# Sheet3.net
KiCad netlist of a schematic drawn in Altium Designer
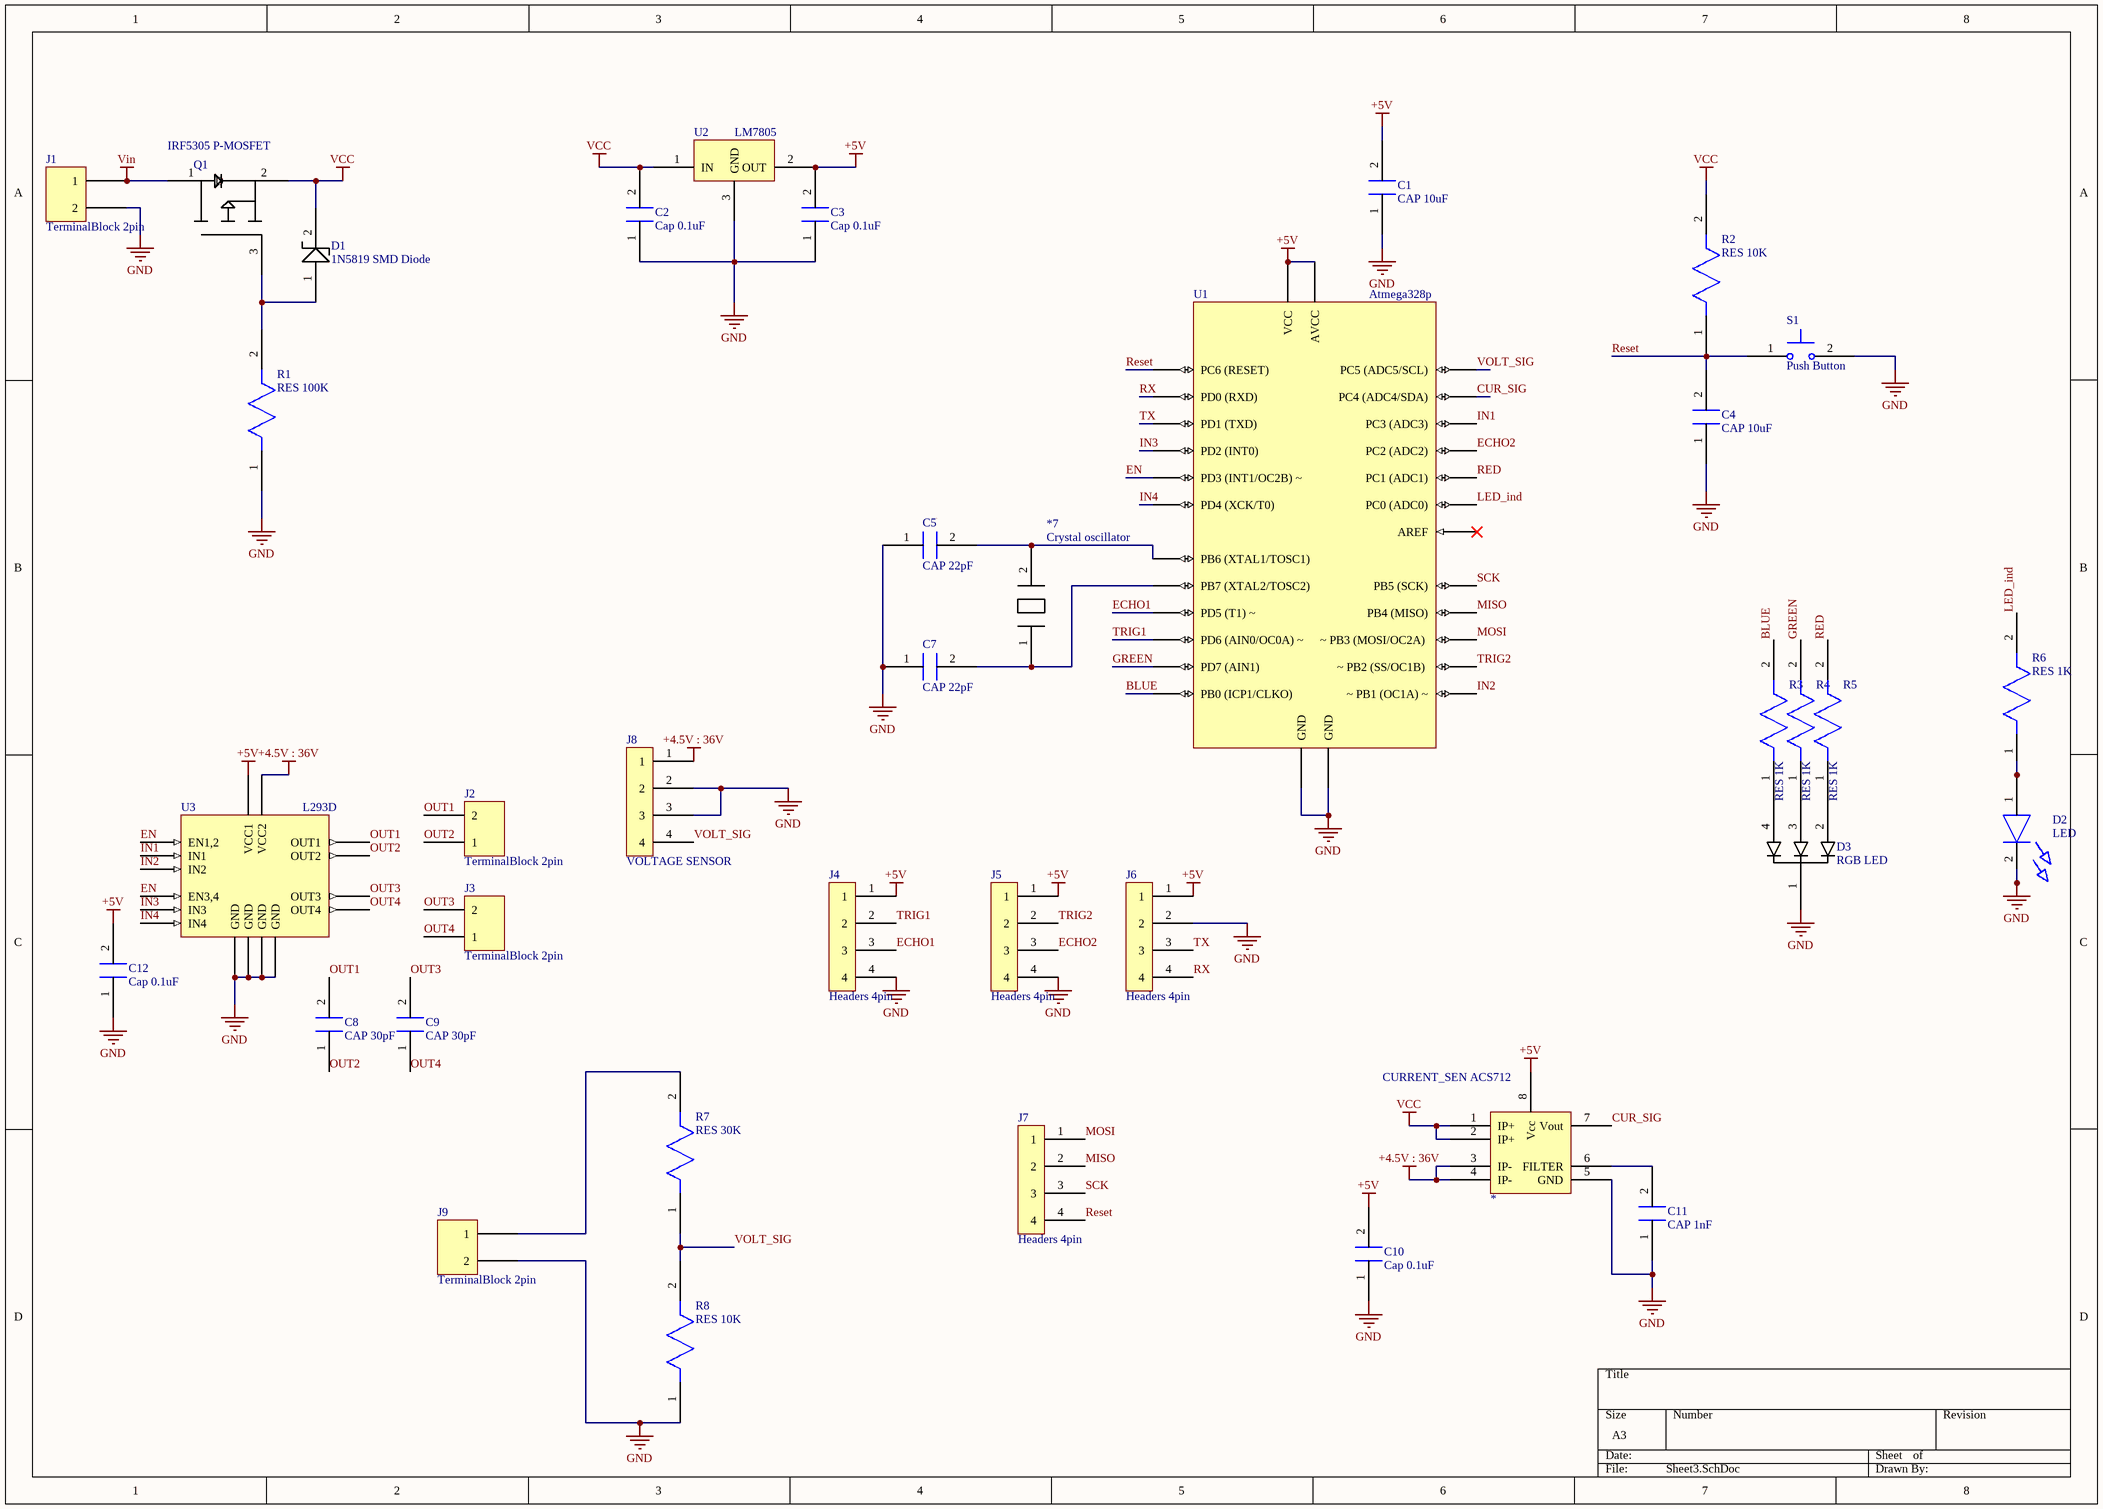
[diagram p0: Sheet3.SchDoc]

(export (version "E")
  (design (tool "Eeschema 10.0.6"))
  (components
    (comp (ref "*")
      (value "CURRENT_SEN ACS712")
      (footprint "Cuurent_sens")
      (libsource (lib "Schlib1") (part "CURRENT_MOD ACS712"))
    )
    (comp (ref "*7")
      (value "Crystal oscillator")
      (footprint "Crrystal 16MHZ")
      (libsource (lib "Schlib1") (part "Crystal oscillator"))
    )
    (comp (ref "C1") (value "CAP 10uF") (footprint "Cap 10uF") (libsource (lib "Schlib1") (part "CAP 10uF")))
    (comp (ref "C2")
      (value "Cap 0.1uF")
      (footprint "CAP 0.1uF")
      (libsource (lib "Schlib1") (part "Cap 0.1uF"))
    )
    (comp (ref "C3")
      (value "Cap 0.1uF")
      (footprint "CAP 0.1uF")
      (libsource (lib "Schlib1") (part "Cap 0.1uF"))
    )
    (comp (ref "C4") (value "CAP 10uF") (footprint "Cap 10uF") (libsource (lib "Schlib1") (part "CAP 10uF")))
    (comp (ref "C5") (value "CAP 22pF") (footprint "Cap 22pF") (libsource (lib "Schlib1") (part "CAP 22pF")))
    (comp (ref "C7") (value "CAP 22pF") (footprint "Cap 22pF") (libsource (lib "Schlib1") (part "CAP 22pF")))
    (comp (ref "C8") (value "CAP 30pF") (footprint "CAP 30pF") (libsource (lib "Schlib1") (part "CAP 30pF")))
    (comp (ref "C9") (value "CAP 30pF") (footprint "CAP 30pF") (libsource (lib "Schlib1") (part "CAP 30pF")))
    (comp (ref "C10")
      (value "Cap 0.1uF")
      (footprint "CAP 0.1uF")
      (libsource (lib "Schlib1") (part "Cap 0.1uF"))
    )
    (comp (ref "C11") (value "CAP 1nF") (footprint "CAP 1nF") (libsource (lib "Schlib1") (part "CAP 1nF")))
    (comp (ref "C12")
      (value "Cap 0.1uF")
      (footprint "CAP 0.1uF")
      (libsource (lib "Schlib1") (part "Cap 0.1uF"))
    )
    (comp (ref "D1")
      (value "1N5819 SMD Diode")
      (footprint "1N5819 SMD Diode")
      (libsource (lib "Schlib1") (part "1N5819 SMD Diode"))
    )
    (comp (ref "D2") (value "LED") (footprint "LED") (libsource (lib "Schlib1") (part "LED")))
    (comp (ref "D3") (value "RGB LED") (footprint "RGB LED") (libsource (lib "Schlib1") (part "RGB LED")))
    (comp (ref "J1")
      (value "TerminalBlock 2pin")
      (footprint "Terminal Block 2pin")
      (libsource (lib "Schlib1") (part "TerminalBlock 2pin"))
    )
    (comp (ref "J2")
      (value "TerminalBlock 2pin")
      (footprint "Terminal Block 2pin")
      (libsource (lib "") (part "TerminalBlock 2pin_1"))
    )
    (comp (ref "J3")
      (value "TerminalBlock 2pin")
      (footprint "Terminal Block 2pin")
      (libsource (lib "") (part "TerminalBlock 2pin_1"))
    )
    (comp (ref "J4")
      (value "Headers 4pin")
      (footprint "Header 4pin")
      (libsource (lib "Schlib1") (part "Headers 4pin"))
    )
    (comp (ref "J5")
      (value "Headers 4pin")
      (footprint "Header 4pin")
      (libsource (lib "Schlib1") (part "Headers 4pin"))
    )
    (comp (ref "J6")
      (value "Headers 4pin")
      (footprint "Header 4pin")
      (libsource (lib "Schlib1") (part "Headers 4pin"))
    )
    (comp (ref "J7")
      (value "Headers 4pin")
      (footprint "Header 4pin")
      (libsource (lib "Schlib1") (part "Headers 4pin"))
    )
    (comp (ref "J8")
      (value "VOLTAGE SENSOR")
      (footprint "Header 4pin")
      (libsource (lib "Schlib1") (part "Headers 4pin"))
    )
    (comp (ref "J9")
      (value "TerminalBlock 2pin")
      (footprint "Terminal Block 2pin")
      (libsource (lib "Schlib1") (part "TerminalBlock 2pin"))
    )
    (comp (ref "Q1")
      (value "IRF5305 P-MOSFET")
      (footprint "IRF5305")
      (libsource (lib "Schlib1") (part "IRF5305 P-MOSFET"))
    )
    (comp (ref "R1") (value "RES 100K") (footprint "Res100K") (libsource (lib "Schlib1") (part "RES 100K")))
    (comp (ref "R2") (value "RES 10K") (footprint "Res10K") (libsource (lib "Schlib1") (part "RES 10K")))
    (comp (ref "R3") (value "RES 1K") (footprint "Res 1K") (libsource (lib "Schlib1") (part "RES 1K")))
    (comp (ref "R4") (value "RES 1K") (footprint "Res 1K") (libsource (lib "Schlib1") (part "RES 1K")))
    (comp (ref "R5") (value "RES 1K") (footprint "Res 1K") (libsource (lib "Schlib1") (part "RES 1K")))
    (comp (ref "R6") (value "RES 1K") (footprint "Res 1K") (libsource (lib "Schlib1") (part "RES 1K")))
    (comp (ref "R7") (value "RES 30K") (footprint "Res100K") (libsource (lib "Schlib1") (part "RES 100K")))
    (comp (ref "R8") (value "RES 10K") (footprint "Res10K") (libsource (lib "Schlib1") (part "RES 10K")))
    (comp (ref "S1")
      (value "Push Button")
      (footprint "Push Button")
      (libsource (lib "Schlib1") (part "Push Button"))
    )
    (comp (ref "U1")
      (value "Atmega328p")
      (footprint "ATMega 328 P-PU - duplicate")
      (libsource (lib "Schlib1") (part "Atmega328p"))
    )
    (comp (ref "U2") (value "LM7805") (footprint "LM7805") (libsource (lib "Schlib1") (part "LM7805")))
    (comp (ref "U3") (value "L293D") (footprint "L293D") (libsource (lib "Schlib1") (part "L293D")))
  )
  (nets
    (net (code "1") (name "+4.5V : 36V") (class "Default")
      (node (ref "*") (pin "3") (pinfunction "IP-_3") (pintype "passive"))
      (node (ref "*") (pin "4") (pinfunction "IP-_4") (pintype "passive"))
      (node (ref "J8") (pin "1") (pinfunction "1_1") (pintype "passive"))
      (node (ref "U3") (pin "8") (pinfunction "VCC2_8") (pintype "power_in"))
    )
    (net (code "2") (name "+5V") (class "Default")
      (node (ref "*") (pin "8") (pinfunction "Vcc_8") (pintype "passive"))
      (node (ref "C1") (pin "2") (pinfunction "2_2") (pintype "passive"))
      (node (ref "C10") (pin "2") (pinfunction "2_2") (pintype "passive"))
      (node (ref "C12") (pin "2") (pinfunction "2_2") (pintype "passive"))
      (node (ref "C3") (pin "2") (pinfunction "2_2") (pintype "passive"))
      (node (ref "J4") (pin "1") (pinfunction "1_1") (pintype "passive"))
      (node (ref "J5") (pin "1") (pinfunction "1_1") (pintype "passive"))
      (node (ref "J6") (pin "1") (pinfunction "1_1") (pintype "passive"))
      (node (ref "U1") (pin "20") (pinfunction "AVCC_20") (pintype "passive"))
      (node (ref "U1") (pin "7") (pinfunction "VCC_7") (pintype "passive"))
      (node (ref "U2") (pin "2") (pinfunction "OUT_2") (pintype "passive"))
      (node (ref "U3") (pin "16") (pinfunction "VCC1_16") (pintype "power_in"))
    )
    (net (code "4") (name "/BLUE") (class "Default")
      (node (ref "R3") (pin "2") (pinfunction "4_2") (pintype "passive"))
      (node (ref "U1") (pin "14") (pinfunction "PB0_(ICP1/CLKO)_14") (pintype "bidirectional"))
    )
    (net (code "5") (name "/CUR_SIG") (class "Default")
      (node (ref "*") (pin "7") (pinfunction "Vout_7") (pintype "passive"))
      (node (ref "U1") (pin "27") (pinfunction "PC4_(ADC4/SDA)_27") (pintype "bidirectional"))
    )
    (net (code "6") (name "/ECHO1") (class "Default")
      (node (ref "J4") (pin "3") (pinfunction "3_3") (pintype "passive"))
      (node (ref "U1") (pin "11") (pinfunction "PD5_(T1)_~_11") (pintype "bidirectional"))
    )
    (net (code "7") (name "/ECHO2") (class "Default")
      (node (ref "J5") (pin "3") (pinfunction "3_3") (pintype "passive"))
      (node (ref "U1") (pin "25") (pinfunction "PC2_(ADC2)_25") (pintype "bidirectional"))
    )
    (net (code "8") (name "/EN") (class "Default")
      (node (ref "U1") (pin "5") (pinfunction "PD3_(INT1/OC2B)_~_5") (pintype "bidirectional"))
      (node (ref "U3") (pin "1") (pinfunction "EN1,2_1") (pintype "input"))
      (node (ref "U3") (pin "9") (pinfunction "EN3,4_9") (pintype "input"))
    )
    (net (code "9") (name "/GREEN") (class "Default")
      (node (ref "R4") (pin "2") (pinfunction "4_2") (pintype "passive"))
      (node (ref "U1") (pin "13") (pinfunction "PD7_(AIN1)_13") (pintype "bidirectional"))
    )
    (net (code "10") (name "/IN1") (class "Default")
      (node (ref "U1") (pin "26") (pinfunction "PC3_(ADC3)_26") (pintype "bidirectional"))
      (node (ref "U3") (pin "2") (pinfunction "IN1_2") (pintype "input"))
    )
    (net (code "11") (name "/IN2") (class "Default")
      (node (ref "U1") (pin "15") (pinfunction "~_PB1_(OC1A)_~_15") (pintype "bidirectional"))
      (node (ref "U3") (pin "7") (pinfunction "IN2_7") (pintype "input"))
    )
    (net (code "12") (name "/IN3") (class "Default")
      (node (ref "U1") (pin "4") (pinfunction "PD2_(INT0)_4") (pintype "bidirectional"))
      (node (ref "U3") (pin "10") (pinfunction "IN3_10") (pintype "input"))
    )
    (net (code "13") (name "/IN4") (class "Default")
      (node (ref "U1") (pin "6") (pinfunction "PD4_(XCK/T0)_6") (pintype "bidirectional"))
      (node (ref "U3") (pin "15") (pinfunction "IN4_15") (pintype "input"))
    )
    (net (code "14") (name "/LED_ind") (class "Default")
      (node (ref "R6") (pin "2") (pinfunction "4_2") (pintype "passive"))
      (node (ref "U1") (pin "23") (pinfunction "PC0_(ADC0)_23") (pintype "bidirectional"))
    )
    (net (code "15") (name "/MISO") (class "Default")
      (node (ref "J7") (pin "2") (pinfunction "2_2") (pintype "passive"))
      (node (ref "U1") (pin "18") (pinfunction "PB4_(MISO)_18") (pintype "bidirectional"))
    )
    (net (code "16") (name "/MOSI") (class "Default")
      (node (ref "J7") (pin "1") (pinfunction "1_1") (pintype "passive"))
      (node (ref "U1") (pin "17") (pinfunction "~_PB3_(MOSI/OC2A)_17") (pintype "bidirectional"))
    )
    (net (code "17") (name "/OUT1") (class "Default")
      (node (ref "C8") (pin "2") (pinfunction "2_2") (pintype "passive"))
      (node (ref "J2") (pin "2") (pinfunction "2_2") (pintype "passive"))
      (node (ref "U3") (pin "3") (pinfunction "OUT1_3") (pintype "output"))
    )
    (net (code "18") (name "/OUT2") (class "Default")
      (node (ref "C8") (pin "1") (pinfunction "1_1") (pintype "passive"))
      (node (ref "J2") (pin "1") (pinfunction "1_1") (pintype "passive"))
      (node (ref "U3") (pin "6") (pinfunction "OUT2_6") (pintype "output"))
    )
    (net (code "19") (name "/OUT3") (class "Default")
      (node (ref "C9") (pin "2") (pinfunction "2_2") (pintype "passive"))
      (node (ref "J3") (pin "2") (pinfunction "2_2") (pintype "passive"))
      (node (ref "U3") (pin "11") (pinfunction "OUT3_11") (pintype "output"))
    )
    (net (code "20") (name "/OUT4") (class "Default")
      (node (ref "C9") (pin "1") (pinfunction "1_1") (pintype "passive"))
      (node (ref "J3") (pin "1") (pinfunction "1_1") (pintype "passive"))
      (node (ref "U3") (pin "14") (pinfunction "OUT4_14") (pintype "output"))
    )
    (net (code "21") (name "/RED") (class "Default")
      (node (ref "R5") (pin "2") (pinfunction "4_2") (pintype "passive"))
      (node (ref "U1") (pin "24") (pinfunction "PC1_(ADC1)_24") (pintype "bidirectional"))
    )
    (net (code "22") (name "/RX") (class "Default")
      (node (ref "J6") (pin "4") (pinfunction "4_4") (pintype "passive"))
      (node (ref "U1") (pin "2") (pinfunction "PD0_(RXD)_2") (pintype "bidirectional"))
    )
    (net (code "23") (name "/Reset") (class "Default")
      (node (ref "C4") (pin "2") (pinfunction "2_2") (pintype "passive"))
      (node (ref "J7") (pin "4") (pinfunction "4_4") (pintype "passive"))
      (node (ref "R2") (pin "1") (pinfunction "3_1") (pintype "passive"))
      (node (ref "S1") (pin "1") (pinfunction "76_1") (pintype "passive"))
      (node (ref "U1") (pin "1") (pinfunction "PC6_(RESET)_1") (pintype "bidirectional"))
    )
    (net (code "24") (name "/SCK") (class "Default")
      (node (ref "J7") (pin "3") (pinfunction "3_3") (pintype "passive"))
      (node (ref "U1") (pin "19") (pinfunction "PB5_(SCK)_19") (pintype "bidirectional"))
    )
    (net (code "25") (name "/TRIG1") (class "Default")
      (node (ref "J4") (pin "2") (pinfunction "2_2") (pintype "passive"))
      (node (ref "U1") (pin "12") (pinfunction "PD6_(AIN0/OC0A)_~_12") (pintype "bidirectional"))
    )
    (net (code "26") (name "/TRIG2") (class "Default")
      (node (ref "J5") (pin "2") (pinfunction "2_2") (pintype "passive"))
      (node (ref "U1") (pin "16") (pinfunction "~_PB2_(SS/OC1B)_16") (pintype "bidirectional"))
    )
    (net (code "27") (name "/TX") (class "Default")
      (node (ref "J6") (pin "3") (pinfunction "3_3") (pintype "passive"))
      (node (ref "U1") (pin "3") (pinfunction "PD1_(TXD)_3") (pintype "bidirectional"))
    )
    (net (code "28") (name "/VOLT_SIG") (class "Default")
      (node (ref "J8") (pin "4") (pinfunction "4_4") (pintype "passive"))
      (node (ref "R7") (pin "1") (pinfunction "3_1") (pintype "passive"))
      (node (ref "R8") (pin "2") (pinfunction "4_2") (pintype "passive"))
      (node (ref "U1") (pin "28") (pinfunction "PC5_(ADC5/SCL)_28") (pintype "bidirectional"))
    )
    (net (code "29") (name "GND") (class "Default")
      (node (ref "*") (pin "5") (pinfunction "GND_5") (pintype "passive"))
      (node (ref "C1") (pin "1") (pinfunction "1_1") (pintype "passive"))
      (node (ref "C10") (pin "1") (pinfunction "1_1") (pintype "passive"))
      (node (ref "C11") (pin "1") (pinfunction "1_1") (pintype "passive"))
      (node (ref "C12") (pin "1") (pinfunction "1_1") (pintype "passive"))
      (node (ref "C2") (pin "1") (pinfunction "1_1") (pintype "passive"))
      (node (ref "C3") (pin "1") (pinfunction "1_1") (pintype "passive"))
      (node (ref "C4") (pin "1") (pinfunction "1_1") (pintype "passive"))
      (node (ref "C5") (pin "1") (pinfunction "1_1") (pintype "passive"))
      (node (ref "C7") (pin "1") (pinfunction "1_1") (pintype "passive"))
      (node (ref "D2") (pin "2") (pinfunction "6_2") (pintype "passive"))
      (node (ref "D3") (pin "1") (pinfunction "(-)_1") (pintype "passive"))
      (node (ref "J1") (pin "2") (pinfunction "2_2") (pintype "passive"))
      (node (ref "J4") (pin "4") (pinfunction "4_4") (pintype "passive"))
      (node (ref "J5") (pin "4") (pinfunction "4_4") (pintype "passive"))
      (node (ref "J6") (pin "2") (pinfunction "2_2") (pintype "passive"))
      (node (ref "J8") (pin "2") (pinfunction "2_2") (pintype "passive"))
      (node (ref "J8") (pin "3") (pinfunction "3_3") (pintype "passive"))
      (node (ref "J9") (pin "2") (pinfunction "2_2") (pintype "passive"))
      (node (ref "R1") (pin "1") (pinfunction "3_1") (pintype "passive"))
      (node (ref "R8") (pin "1") (pinfunction "3_1") (pintype "passive"))
      (node (ref "S1") (pin "2") (pinfunction "77_2") (pintype "passive"))
      (node (ref "U1") (pin "22") (pinfunction "GND_22") (pintype "passive"))
      (node (ref "U1") (pin "8") (pinfunction "GND_8") (pintype "passive"))
      (node (ref "U2") (pin "3") (pinfunction "GND_3") (pintype "power_in"))
      (node (ref "U3") (pin "12") (pinfunction "GND_12") (pintype "power_in"))
      (node (ref "U3") (pin "13") (pinfunction "GND_13") (pintype "power_in"))
      (node (ref "U3") (pin "4") (pinfunction "GND_4") (pintype "power_in"))
      (node (ref "U3") (pin "5") (pinfunction "GND_5") (pintype "power_in"))
    )
    (net (code "30") (name "Net-(*-FILTER)") (class "Default")
      (node (ref "*") (pin "6") (pinfunction "FILTER_6") (pintype "passive"))
      (node (ref "C11") (pin "2") (pinfunction "2_2") (pintype "passive"))
    )
    (net (code "31") (name "Net-(D2-7)") (class "Default")
      (node (ref "D2") (pin "1") (pinfunction "7_1") (pintype "passive"))
      (node (ref "R6") (pin "1") (pinfunction "3_1") (pintype "passive"))
    )
    (net (code "32") (name "Net-(D3-B)") (class "Default")
      (node (ref "D3") (pin "4") (pinfunction "B_4") (pintype "passive"))
      (node (ref "R3") (pin "1") (pinfunction "3_1") (pintype "passive"))
    )
    (net (code "33") (name "Net-(D3-G)") (class "Default")
      (node (ref "D3") (pin "3") (pinfunction "G_3") (pintype "passive"))
      (node (ref "R4") (pin "1") (pinfunction "3_1") (pintype "passive"))
    )
    (net (code "34") (name "Net-(D3-R)") (class "Default")
      (node (ref "D3") (pin "2") (pinfunction "R_2") (pintype "passive"))
      (node (ref "R5") (pin "1") (pinfunction "3_1") (pintype "passive"))
    )
    (net (code "35") (name "Net-(Q1-G)") (class "Default")
      (node (ref "D1") (pin "1") (pinfunction "1_1") (pintype "passive"))
      (node (ref "Q1") (pin "3") (pinfunction "G_3") (pintype "passive"))
      (node (ref "R1") (pin "2") (pinfunction "4_2") (pintype "passive"))
    )
    (net (code "36") (name "Net-(R7-4)") (class "Default")
      (node (ref "J9") (pin "1") (pinfunction "1_1") (pintype "passive"))
      (node (ref "R7") (pin "2") (pinfunction "4_2") (pintype "passive"))
    )
    (net (code "37") (name "Net-(U1-PB6_(XTAL1{slash}TOSC1))") (class "Default")
      (node (ref "*7") (pin "2") (pinfunction "2_2") (pintype "passive"))
      (node (ref "C5") (pin "2") (pinfunction "2_2") (pintype "passive"))
      (node (ref "U1") (pin "9") (pinfunction "PB6_(XTAL1/TOSC1)_9") (pintype "bidirectional"))
    )
    (net (code "38") (name "Net-(U1-PB7_(XTAL2{slash}TOSC2))") (class "Default")
      (node (ref "*7") (pin "1") (pinfunction "1_1") (pintype "passive"))
      (node (ref "C7") (pin "2") (pinfunction "2_2") (pintype "passive"))
      (node (ref "U1") (pin "10") (pinfunction "PB7_(XTAL2/TOSC2)_10") (pintype "bidirectional"))
    )
    (net (code "39") (name "VCC") (class "Default")
      (node (ref "*") (pin "1") (pinfunction "IP+_1") (pintype "passive"))
      (node (ref "*") (pin "2") (pinfunction "IP+_2") (pintype "passive"))
      (node (ref "C2") (pin "2") (pinfunction "2_2") (pintype "passive"))
      (node (ref "D1") (pin "2") (pinfunction "2_2") (pintype "passive"))
      (node (ref "Q1") (pin "2") (pinfunction "S_2") (pintype "passive"))
      (node (ref "R2") (pin "2") (pinfunction "4_2") (pintype "passive"))
      (node (ref "U2") (pin "1") (pinfunction "IN_1") (pintype "passive"))
    )
    (net (code "40") (name "Vin") (class "Default")
      (node (ref "J1") (pin "1") (pinfunction "1_1") (pintype "passive"))
      (node (ref "Q1") (pin "1") (pinfunction "D_1") (pintype "passive"))
    )
    (net (code "41") (name "unconnected-(U1-AREF-Pad21)") (class "Default")
      (node (ref "U1") (pin "21") (pinfunction "AREF_21") (pintype "input+no_connect"))
    )
  )
)
